# 7b_-_High_Current_Path_Detection.net
KiCad netlist of a schematic drawn in Altium Designer
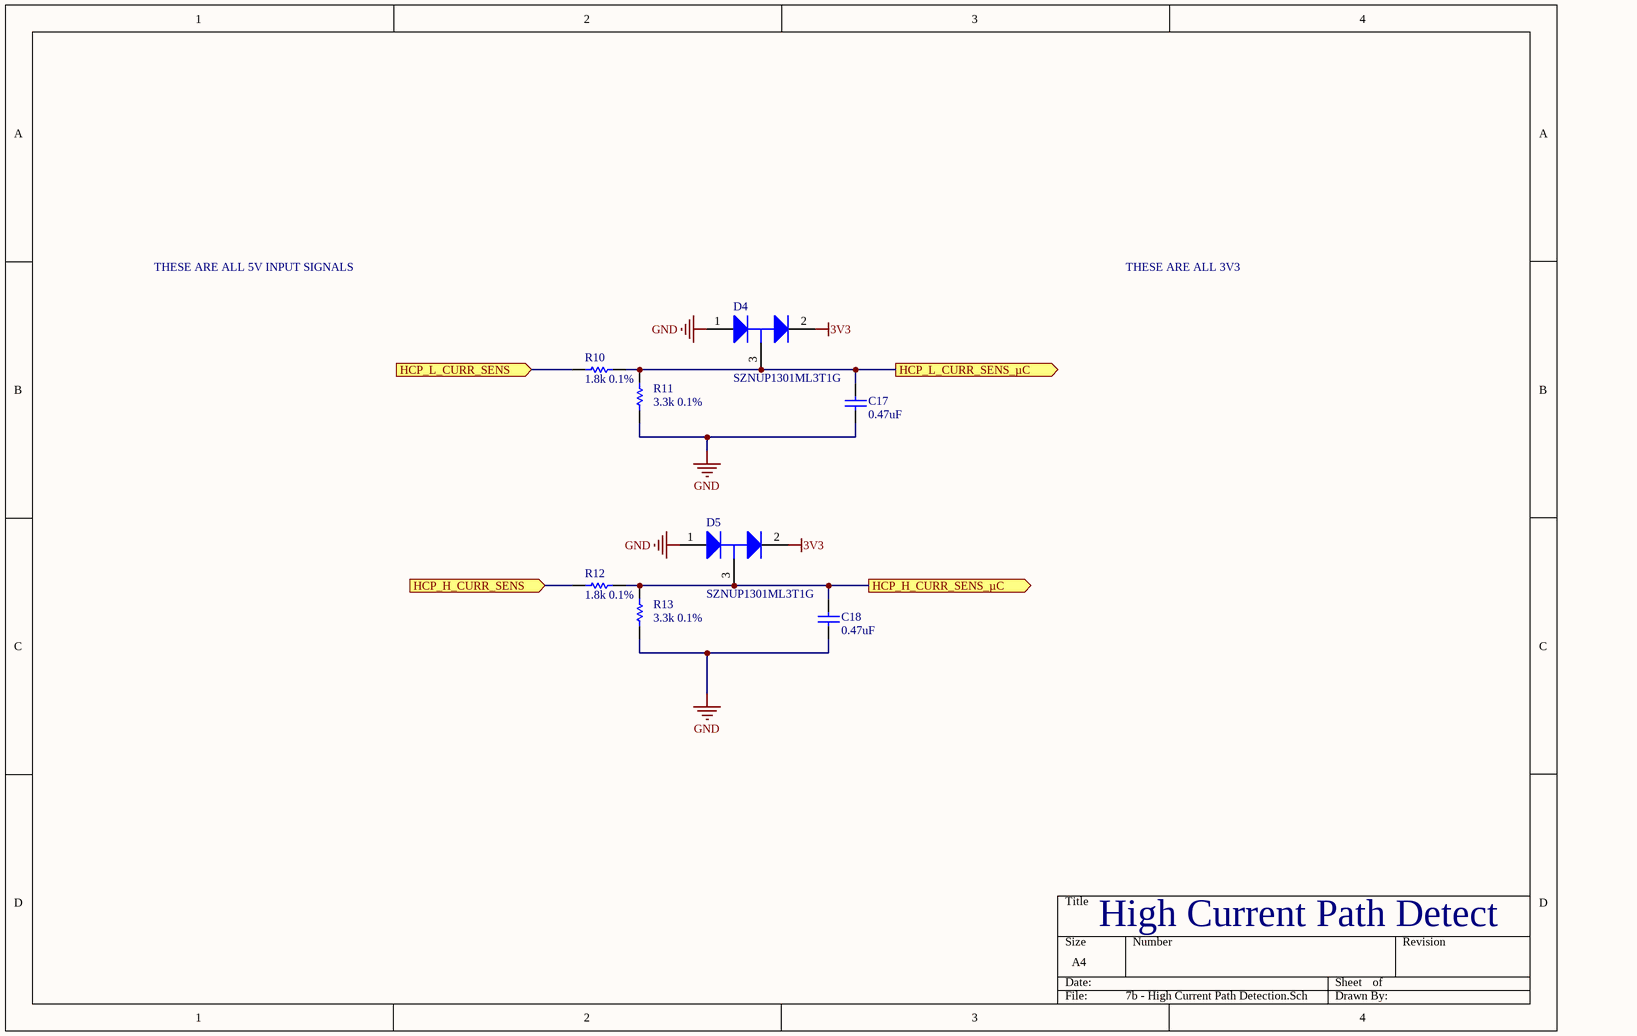
[diagram p0: 7b - High Current Path Detection.SchDoc]

(export (version "E")
  (design (tool "Eeschema 10.0.6"))
  (components
    (comp (ref "C17")
      (value "0.47uF")
      (footprint "1608[0603]")
      (description "Capacitor")
      (fields (field (name "Comment") "Cap") (field (name "PUBLISHER") "Altium Limited"))
      (libsource (lib "Miscellaneous Devices") (part "Cap"))
    )
    (comp (ref "C18")
      (value "0.47uF")
      (footprint "1608[0603]")
      (description "Capacitor")
      (fields (field (name "Comment") "Cap") (field (name "PUBLISHER") "Altium Limited"))
      (libsource (lib "Miscellaneous Devices") (part "Cap"))
    )
    (comp (ref "D4")
      (value "SZNUP1301ML3T1G")
      (footprint "ONSC-SOT-23-3-318-08_V")
      (fields (field (name "MANUFACTURER") "On Semiconductor"))
      (libsource (lib "Altium Content Vault") (part "ONSC-NUP1301-SOT-23-3-318-08"))
    )
    (comp (ref "D5")
      (value "SZNUP1301ML3T1G")
      (footprint "ONSC-SOT-23-3-318-08_V")
      (fields (field (name "MANUFACTURER") "On Semiconductor"))
      (libsource (lib "Altium Content Vault") (part "ONSC-NUP1301-SOT-23-3-318-08"))
    )
    (comp (ref "R10")
      (value "1.8k 0.1%")
      (footprint "1608[0603]")
      (description "Resistor")
      (fields (field (name "Comment") "Res1") (field (name "PUBLISHER") "Altium Limited"))
      (libsource (lib "Miscellaneous Devices") (part "Res1"))
    )
    (comp (ref "R11")
      (value "3.3k 0.1%")
      (footprint "1608[0603]")
      (description "Resistor")
      (fields (field (name "Comment") "Res1") (field (name "PUBLISHER") "Altium Limited"))
      (libsource (lib "Miscellaneous Devices") (part "Res1"))
    )
    (comp (ref "R12")
      (value "1.8k 0.1%")
      (footprint "1608[0603]")
      (description "Resistor")
      (fields (field (name "Comment") "Res1") (field (name "PUBLISHER") "Altium Limited"))
      (libsource (lib "Miscellaneous Devices") (part "Res1"))
    )
    (comp (ref "R13")
      (value "3.3k 0.1%")
      (footprint "1608[0603]")
      (description "Resistor")
      (fields (field (name "Comment") "Res1") (field (name "PUBLISHER") "Altium Limited"))
      (libsource (lib "Miscellaneous Devices") (part "Res1"))
    )
  )
  (nets
    (net (code "1") (name "/HCP_H_CURR_SENS") (class "Default")
      (node (ref "R12") (pin "2") (pinfunction "2_2") (pintype "passive"))
    )
    (net (code "2") (name "/HCP_H_CURR_SENS_µC") (class "Default")
      (node (ref "C18") (pin "2") (pinfunction "2_2") (pintype "passive"))
      (node (ref "D5") (pin "3") (pinfunction "K/A_3") (pintype "passive"))
      (node (ref "R12") (pin "1") (pinfunction "1_1") (pintype "passive"))
      (node (ref "R13") (pin "2") (pinfunction "2_2") (pintype "passive"))
    )
    (net (code "3") (name "/HCP_L_CURR_SENS") (class "Default")
      (node (ref "R10") (pin "2") (pinfunction "2_2") (pintype "passive"))
    )
    (net (code "4") (name "/HCP_L_CURR_SENS_µC") (class "Default")
      (node (ref "C17") (pin "2") (pinfunction "2_2") (pintype "passive"))
      (node (ref "D4") (pin "3") (pinfunction "K/A_3") (pintype "passive"))
      (node (ref "R10") (pin "1") (pinfunction "1_1") (pintype "passive"))
      (node (ref "R11") (pin "2") (pinfunction "2_2") (pintype "passive"))
    )
    (net (code "5") (name "3V3") (class "Default")
      (node (ref "D4") (pin "2") (pinfunction "K_2") (pintype "passive"))
      (node (ref "D5") (pin "2") (pinfunction "K_2") (pintype "passive"))
    )
    (net (code "6") (name "GND") (class "Default")
      (node (ref "C17") (pin "1") (pinfunction "1_1") (pintype "passive"))
      (node (ref "C18") (pin "1") (pinfunction "1_1") (pintype "passive"))
      (node (ref "D4") (pin "1") (pinfunction "A_1") (pintype "passive"))
      (node (ref "D5") (pin "1") (pinfunction "A_1") (pintype "passive"))
      (node (ref "R11") (pin "1") (pinfunction "1_1") (pintype "passive"))
      (node (ref "R13") (pin "1") (pinfunction "1_1") (pintype "passive"))
    )
  )
)
